# 2015_BeaconLed.net
KiCad netlist of a schematic drawn in Altium Designer
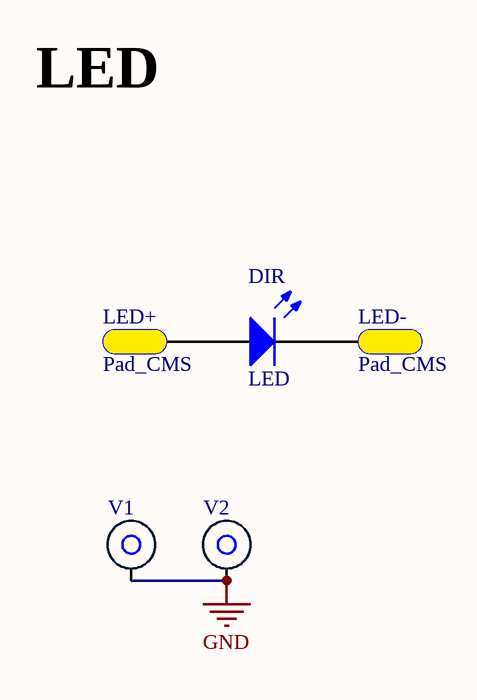
[diagram p0: 2015_BeaconLed.SchDoc]

(export (version "E")
  (design (tool "Eeschema 10.0.6"))
  (components
    (comp (ref "DIR")
      (value "LED")
      (footprint "Led_5mm")
      (description "Typical RED, GREEN, YELLOW, AMBER GaAs LED")
      (fields (field (name "PUBLISHER") "Altium Limited"))
      (libsource (lib "Robot2010") (part "LED"))
    )
    (comp (ref "LED+")
      (value "Pad_CMS")
      (footprint "PAD_CMS_5.08x2.54")
      (description "Pad pour souder un fil")
      (fields (field (name "PUBLISHER") "Damien Guitton"))
      (libsource (lib "DG_Connecteur") (part "Pad_CMS"))
    )
    (comp (ref "LED-")
      (value "Pad_CMS")
      (footprint "PAD_CMS_5.08x2.54")
      (description "Pad pour souder un fil")
      (fields (field (name "PUBLISHER") "Damien Guitton"))
      (libsource (lib "DG_Connecteur") (part "Pad_CMS"))
    )
    (comp (ref "V1")
      (value "Entretoise WURTH CMS")
      (footprint "ENTRETOISE_CMS")
      (description "Entretoise Wurth")
      (fields (field (name "PUBLISHER") "Damien Guitton"))
      (libsource (lib "_ROBOT") (part "Entretoise WURTH CMS"))
    )
    (comp (ref "V2")
      (value "Entretoise WURTH CMS")
      (footprint "ENTRETOISE_CMS")
      (description "Entretoise Wurth")
      (fields (field (name "PUBLISHER") "Damien Guitton"))
      (libsource (lib "_ROBOT") (part "Entretoise WURTH CMS"))
    )
  )
  (nets
    (net (code "1") (name "GND") (class "Default")
      (node (ref "V1") (pin "1") (pinfunction "1_1") (pintype "passive"))
      (node (ref "V2") (pin "1") (pinfunction "1_1") (pintype "passive"))
    )
    (net (code "2") (name "Net-(DIR-Pad1)") (class "Default")
      (node (ref "DIR") (pin "1") (pinfunction "1_1") (pintype "passive"))
      (node (ref "LED+") (pin "1") (pinfunction "1_1") (pintype "passive"))
    )
    (net (code "3") (name "Net-(DIR-Pad2)") (class "Default")
      (node (ref "DIR") (pin "2") (pinfunction "2_2") (pintype "passive"))
      (node (ref "LED-") (pin "1") (pinfunction "1_1") (pintype "passive"))
    )
  )
)
